# decawave-rf.net
KiCad netlist of a schematic drawn in Altium Designer
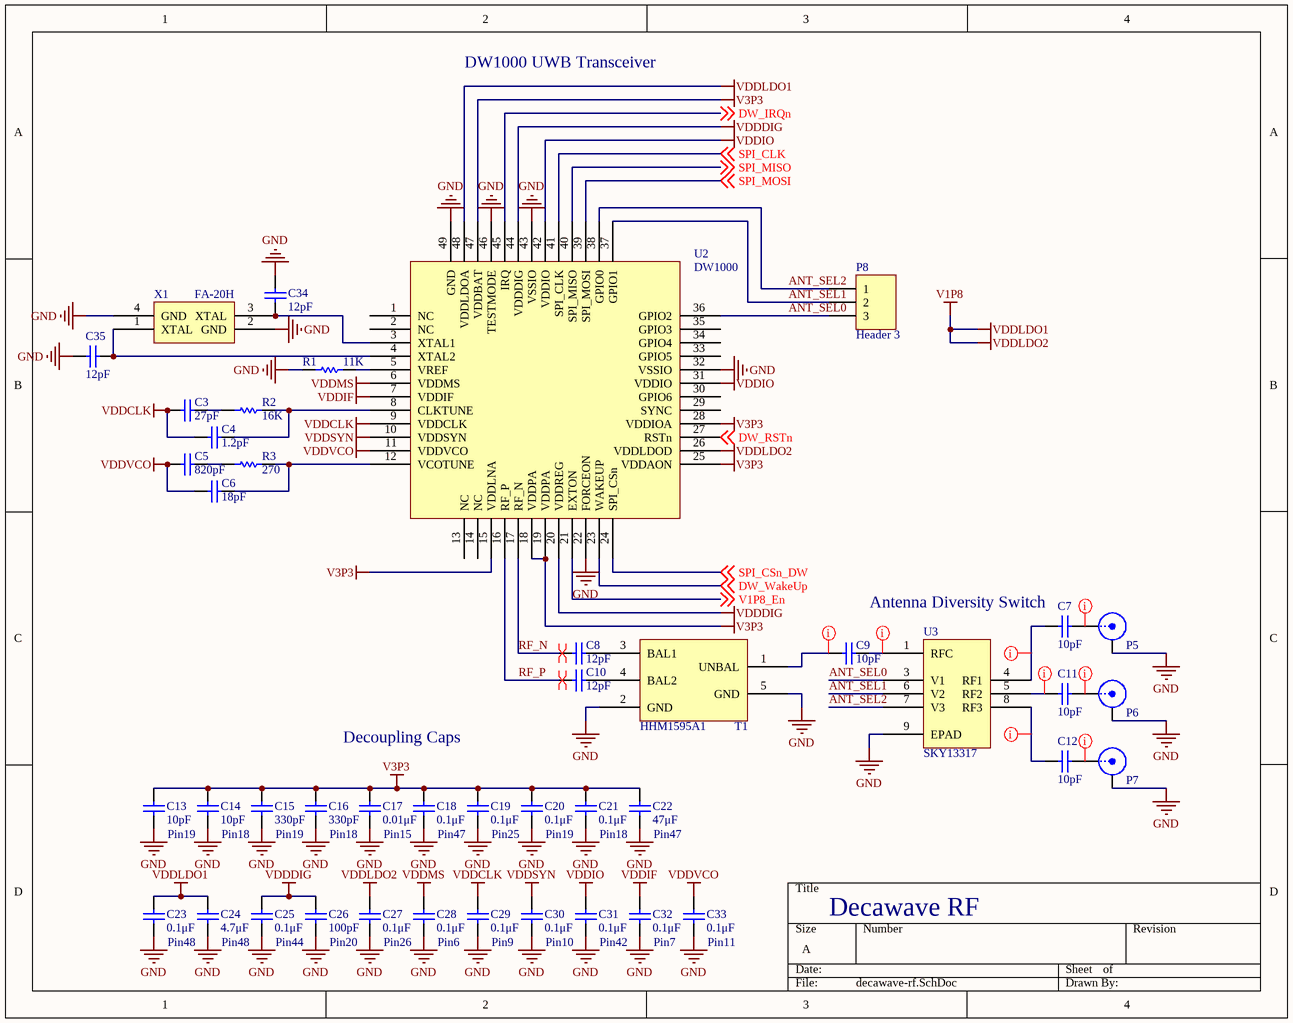
[diagram p0: decawave-rf.SchDoc]

(export (version "E")
  (design (tool "Eeschema 10.0.6"))
  (components
    (comp (ref "C3")
      (value "27pF")
      (footprint "0402")
      (description "Capacitor (Semiconductor SIM Model)")
      (fields
        (field (name "DISTPARTNO") "490-5869-1-ND")
        (field (name "MANPARTNO") "GRM1555C1H270JA01D")
        (field (name "PUBLISHER") "Altium Limited")
      )
      (libsource (lib "decawave-lib") (part "Cap Chip"))
    )
    (comp (ref "C4")
      (value "1.2pF")
      (footprint "0402")
      (description "Capacitor (Semiconductor SIM Model)")
      (fields
        (field (name "DISTPARTNO") "490-6209-1-ND")
        (field (name "MANPARTNO") "GRM1555C1H1R2BA01D")
        (field (name "PUBLISHER") "Altium Limited")
      )
      (libsource (lib "decawave-lib") (part "Cap Chip"))
    )
    (comp (ref "C5")
      (value "820pF")
      (footprint "0402")
      (description "Capacitor (Semiconductor SIM Model)")
      (fields
        (field (name "DISTPARTNO") "490-3250-1-ND")
        (field (name "MANPARTNO") "GRM155R71H821KA01D")
        (field (name "PUBLISHER") "Altium Limited")
      )
      (libsource (lib "decawave-lib") (part "Cap Chip"))
    )
    (comp (ref "C6")
      (value "18pF")
      (footprint "0402")
      (description "Capacitor (Semiconductor SIM Model)")
      (fields
        (field (name "DISTPARTNO") "490-5858-1-ND")
        (field (name "MANPARTNO") "GRM1555C1H180JA01D")
        (field (name "PUBLISHER") "Altium Limited")
      )
      (libsource (lib "decawave-lib") (part "Cap Chip"))
    )
    (comp (ref "C7")
      (value "10pF")
      (footprint "0402")
      (description "Capacitor (Semiconductor SIM Model)")
      (fields
        (field (name "DISTPARTNO") "490-3113-1-ND")
        (field (name "MANPARTNO") "GJM1555C1H100JB01D")
        (field (name "PUBLISHER") "Altium Limited")
      )
      (libsource (lib "decawave-lib") (part "Cap Chip"))
    )
    (comp (ref "C8")
      (value "12pF")
      (footprint "0402")
      (description "Capacitor (Semiconductor SIM Model)")
      (fields
        (field (name "DISTPARTNO") "490-3115-1-ND")
        (field (name "MANPARTNO") "GJM1555C1H120JB01D")
        (field (name "PUBLISHER") "Altium Limited")
      )
      (libsource (lib "decawave-lib") (part "Cap Chip"))
    )
    (comp (ref "C9")
      (value "10pF")
      (footprint "0402")
      (description "Capacitor (Semiconductor SIM Model)")
      (fields
        (field (name "DISTPARTNO") "490-3113-1-ND")
        (field (name "MANPARTNO") "GJM1555C1H100JB01D")
        (field (name "PUBLISHER") "Altium Limited")
      )
      (libsource (lib "decawave-lib") (part "Cap Chip"))
    )
    (comp (ref "C10")
      (value "12pF")
      (footprint "0402")
      (description "Capacitor (Semiconductor SIM Model)")
      (fields
        (field (name "DISTPARTNO") "490-3115-1-ND")
        (field (name "MANPARTNO") "GJM1555C1H120JB01D")
        (field (name "PUBLISHER") "Altium Limited")
      )
      (libsource (lib "decawave-lib") (part "Cap Chip"))
    )
    (comp (ref "C11")
      (value "10pF")
      (footprint "0402")
      (description "Capacitor (Semiconductor SIM Model)")
      (fields
        (field (name "DISTPARTNO") "490-3113-1-ND")
        (field (name "MANPARTNO") "GJM1555C1H100JB01D")
        (field (name "PUBLISHER") "Altium Limited")
      )
      (libsource (lib "decawave-lib") (part "Cap Chip"))
    )
    (comp (ref "C12")
      (value "10pF")
      (footprint "0402")
      (description "Capacitor (Semiconductor SIM Model)")
      (fields
        (field (name "DISTPARTNO") "490-3113-1-ND")
        (field (name "MANPARTNO") "GJM1555C1H100JB01D")
        (field (name "PUBLISHER") "Altium Limited")
      )
      (libsource (lib "decawave-lib") (part "Cap Chip"))
    )
    (comp (ref "C13")
      (value "10pF")
      (footprint "0402")
      (description "Capacitor (Semiconductor SIM Model)")
      (fields
        (field (name "PINPLACEMENT") "Pin19")
        (field (name "DISTPARTNO") "490-3113-1-ND")
        (field (name "MANPARTNO") "GJM1555C1H100JB01D")
        (field (name "PUBLISHER") "Altium Limited")
      )
      (libsource (lib "decawave-lib") (part "Cap Chip"))
    )
    (comp (ref "C14")
      (value "10pF")
      (footprint "0402")
      (description "Capacitor (Semiconductor SIM Model)")
      (fields
        (field (name "PINPLACEMENT") "Pin18")
        (field (name "DISTPARTNO") "490-3113-1-ND")
        (field (name "MANPARTNO") "GJM1555C1H100JB01D")
        (field (name "PUBLISHER") "Altium Limited")
      )
      (libsource (lib "decawave-lib") (part "Cap Chip"))
    )
    (comp (ref "C15")
      (value "330pF")
      (footprint "0402")
      (description "Capacitor (Semiconductor SIM Model)")
      (fields
        (field (name "PINPLACEMENT") "Pin19")
        (field (name "DISTPARTNO") "490-1295-1-ND")
        (field (name "MANPARTNO") "GRM1555C1H331JA01D")
        (field (name "PUBLISHER") "Altium Limited")
      )
      (libsource (lib "decawave-lib") (part "Cap Chip"))
    )
    (comp (ref "C16")
      (value "330pF")
      (footprint "0402")
      (description "Capacitor (Semiconductor SIM Model)")
      (fields
        (field (name "PINPLACEMENT") "Pin18")
        (field (name "DISTPARTNO") "490-1295-1-ND")
        (field (name "MANPARTNO") "GRM1555C1H331JA01D")
        (field (name "PUBLISHER") "Altium Limited")
      )
      (libsource (lib "decawave-lib") (part "Cap Chip"))
    )
    (comp (ref "C17")
      (value "0.01μF")
      (footprint "0402")
      (description "Capacitor (Semiconductor SIM Model)")
      (fields
        (field (name "PINPLACEMENT") "Pin15")
        (field (name "DISTPARTNO") "490-1312-1-ND")
        (field (name "MANPARTNO") "GRM155R71E103KA01D")
        (field (name "PUBLISHER") "Altium Limited")
      )
      (libsource (lib "decawave-lib") (part "Cap Chip"))
    )
    (comp (ref "C18")
      (value "0.1μF")
      (footprint "0402")
      (description "Capacitor (Semiconductor SIM Model)")
      (fields
        (field (name "PINPLACEMENT") "Pin47")
        (field (name "DISTPARTNO") "490-3261-1-ND")
        (field (name "MANPARTNO") "GRM155R71C104KA88D")
        (field (name "PUBLISHER") "Altium Limited")
      )
      (libsource (lib "decawave-lib") (part "Cap Chip"))
    )
    (comp (ref "C19")
      (value "0.1μF")
      (footprint "0402")
      (description "Capacitor (Semiconductor SIM Model)")
      (fields
        (field (name "PINPLACEMENT") "Pin25")
        (field (name "DISTPARTNO") "490-3261-1-ND")
        (field (name "MANPARTNO") "GRM155R71C104KA88D")
        (field (name "PUBLISHER") "Altium Limited")
      )
      (libsource (lib "decawave-lib") (part "Cap Chip"))
    )
    (comp (ref "C20")
      (value "0.1μF")
      (footprint "0402")
      (description "Capacitor (Semiconductor SIM Model)")
      (fields
        (field (name "PINPLACEMENT") "Pin19")
        (field (name "DISTPARTNO") "490-3261-1-ND")
        (field (name "MANPARTNO") "GRM155R71C104KA88D")
        (field (name "PUBLISHER") "Altium Limited")
      )
      (libsource (lib "decawave-lib") (part "Cap Chip"))
    )
    (comp (ref "C21")
      (value "0.1μF")
      (footprint "0402")
      (description "Capacitor (Semiconductor SIM Model)")
      (fields
        (field (name "PINPLACEMENT") "Pin18")
        (field (name "DISTPARTNO") "490-3261-1-ND")
        (field (name "MANPARTNO") "GRM155R71C104KA88D")
        (field (name "PUBLISHER") "Altium Limited")
      )
      (libsource (lib "decawave-lib") (part "Cap Chip"))
    )
    (comp (ref "C22")
      (value "47μF")
      (footprint "0805")
      (description "Capacitor (Semiconductor SIM Model)")
      (fields
        (field (name "PINPLACEMENT") "Pin47")
        (field (name "DISTPARTNO") "1276-2420-1-ND")
        (field (name "MANPARTNO") "CL21A476MQCLRNC")
        (field (name "PUBLISHER") "Altium Limited")
      )
      (libsource (lib "decawave-lib") (part "Cap Chip"))
    )
    (comp (ref "C23")
      (value "0.1μF")
      (footprint "0402")
      (description "Capacitor (Semiconductor SIM Model)")
      (fields
        (field (name "PINPLACEMENT") "Pin48")
        (field (name "DISTPARTNO") "490-3261-1-ND")
        (field (name "MANPARTNO") "GRM155R71C104KA88D")
        (field (name "PUBLISHER") "Altium Limited")
      )
      (libsource (lib "decawave-lib") (part "Cap Chip"))
    )
    (comp (ref "C24")
      (value "4.7μF")
      (footprint "0402")
      (description "Capacitor (Semiconductor SIM Model)")
      (fields
        (field (name "PINPLACEMENT") "Pin48")
        (field (name "DISTPARTNO") "445-8023-1-ND")
        (field (name "MANPARTNO") "C1005X5R1A475M050BC")
        (field (name "PUBLISHER") "Altium Limited")
      )
      (libsource (lib "decawave-lib") (part "Cap Chip"))
    )
    (comp (ref "C25")
      (value "0.1μF")
      (footprint "0402")
      (description "Capacitor (Semiconductor SIM Model)")
      (fields
        (field (name "PINPLACEMENT") "Pin44")
        (field (name "DISTPARTNO") "490-3261-1-ND")
        (field (name "MANPARTNO") "GRM155R71C104KA88D")
        (field (name "PUBLISHER") "Altium Limited")
      )
      (libsource (lib "decawave-lib") (part "Cap Chip"))
    )
    (comp (ref "C26")
      (value "100pF")
      (footprint "0402")
      (description "Capacitor (Semiconductor SIM Model)")
      (fields
        (field (name "PINPLACEMENT") "Pin20")
        (field (name "DISTPARTNO") "490-5922-1-ND")
        (field (name "MANPARTNO") "GRM1555C1H101JA01D")
        (field (name "PUBLISHER") "Altium Limited")
      )
      (libsource (lib "decawave-lib") (part "Cap Chip"))
    )
    (comp (ref "C27")
      (value "0.1μF")
      (footprint "0402")
      (description "Capacitor (Semiconductor SIM Model)")
      (fields
        (field (name "PINPLACEMENT") "Pin26")
        (field (name "DISTPARTNO") "490-3261-1-ND")
        (field (name "MANPARTNO") "GRM155R71C104KA88D")
        (field (name "PUBLISHER") "Altium Limited")
      )
      (libsource (lib "decawave-lib") (part "Cap Chip"))
    )
    (comp (ref "C28")
      (value "0.1μF")
      (footprint "0402")
      (description "Capacitor (Semiconductor SIM Model)")
      (fields
        (field (name "PINPLACEMENT") "Pin6")
        (field (name "DISTPARTNO") "490-3261-1-ND")
        (field (name "MANPARTNO") "GRM155R71C104KA88D")
        (field (name "PUBLISHER") "Altium Limited")
      )
      (libsource (lib "decawave-lib") (part "Cap Chip"))
    )
    (comp (ref "C29")
      (value "0.1μF")
      (footprint "0402")
      (description "Capacitor (Semiconductor SIM Model)")
      (fields
        (field (name "PINPLACEMENT") "Pin9")
        (field (name "DISTPARTNO") "490-3261-1-ND")
        (field (name "MANPARTNO") "GRM155R71C104KA88D")
        (field (name "PUBLISHER") "Altium Limited")
      )
      (libsource (lib "decawave-lib") (part "Cap Chip"))
    )
    (comp (ref "C30")
      (value "0.1μF")
      (footprint "0402")
      (description "Capacitor (Semiconductor SIM Model)")
      (fields
        (field (name "PINPLACEMENT") "Pin10")
        (field (name "DISTPARTNO") "490-3261-1-ND")
        (field (name "MANPARTNO") "GRM155R71C104KA88D")
        (field (name "PUBLISHER") "Altium Limited")
      )
      (libsource (lib "decawave-lib") (part "Cap Chip"))
    )
    (comp (ref "C31")
      (value "0.1μF")
      (footprint "0402")
      (description "Capacitor (Semiconductor SIM Model)")
      (fields
        (field (name "PINPLACEMENT") "Pin42")
        (field (name "DISTPARTNO") "490-3261-1-ND")
        (field (name "MANPARTNO") "GRM155R71C104KA88D")
        (field (name "PUBLISHER") "Altium Limited")
      )
      (libsource (lib "decawave-lib") (part "Cap Chip"))
    )
    (comp (ref "C32")
      (value "0.1μF")
      (footprint "0402")
      (description "Capacitor (Semiconductor SIM Model)")
      (fields
        (field (name "PINPLACEMENT") "Pin7")
        (field (name "DISTPARTNO") "490-3261-1-ND")
        (field (name "MANPARTNO") "GRM155R71C104KA88D")
        (field (name "PUBLISHER") "Altium Limited")
      )
      (libsource (lib "decawave-lib") (part "Cap Chip"))
    )
    (comp (ref "C33")
      (value "0.1μF")
      (footprint "0402")
      (description "Capacitor (Semiconductor SIM Model)")
      (fields
        (field (name "PINPLACEMENT") "Pin11")
        (field (name "DISTPARTNO") "490-3261-1-ND")
        (field (name "MANPARTNO") "GRM155R71C104KA88D")
        (field (name "PUBLISHER") "Altium Limited")
      )
      (libsource (lib "decawave-lib") (part "Cap Chip"))
    )
    (comp (ref "C34")
      (value "12pF")
      (footprint "0402")
      (description "Capacitor (Semiconductor SIM Model)")
      (fields
        (field (name "DISTPARTNO") "490-3115-1-ND")
        (field (name "MANPARTNO") "GJM1555C1H120JB01D")
        (field (name "PUBLISHER") "Altium Limited")
      )
      (libsource (lib "decawave-lib") (part "Cap Chip"))
    )
    (comp (ref "C35")
      (value "12pF")
      (footprint "0402")
      (description "Capacitor (Semiconductor SIM Model)")
      (fields
        (field (name "DISTPARTNO") "490-3115-1-ND")
        (field (name "MANPARTNO") "GJM1555C1H120JB01D")
        (field (name "PUBLISHER") "Altium Limited")
      )
      (libsource (lib "decawave-lib") (part "Cap Chip"))
    )
    (comp (ref "P5")
      (value "SMA")
      (footprint "SMA_EDGE")
      (fields (field (name "DISTPARTNO") "CONSMA003.062-ND") (field (name "MANPARTNO") "CONSMA003.062"))
      (libsource (lib "decawave-lib") (part "SMA"))
    )
    (comp (ref "P6")
      (value "SMA")
      (footprint "SMA_EDGE")
      (fields (field (name "DISTPARTNO") "CONSMA003.062-ND") (field (name "MANPARTNO") "CONSMA003.062"))
      (libsource (lib "decawave-lib") (part "SMA"))
    )
    (comp (ref "P7")
      (value "SMA")
      (footprint "SMA_EDGE")
      (fields (field (name "DISTPARTNO") "CONSMA003.062-ND") (field (name "MANPARTNO") "CONSMA003.062"))
      (libsource (lib "decawave-lib") (part "SMA"))
    )
    (comp (ref "P8")
      (value "Header 3")
      (footprint "HDR1X3")
      (description "Header, 3-Pin")
      (fields (field (name "PUBLISHER") "Altium Limited"))
      (libsource (lib "Miscellaneous Connectors") (part "Header 3"))
    )
    (comp (ref "R1")
      (value "11K")
      (footprint "0402")
      (description "Surface-mount resistor")
      (fields
        (field (name "DISTPARTNO") "P11.0KLCT-ND")
        (field (name "MANPARTNO") "ERJ-2RKF1102X")
        (field (name "PUBLISHER") "Altium Limited")
      )
      (libsource (lib "decawave-lib") (part "Res Chip"))
    )
    (comp (ref "R2")
      (value "16K")
      (footprint "0402")
      (description "Surface-mount resistor")
      (fields
        (field (name "DISTPARTNO") "P16.0KLCT-ND")
        (field (name "MANPARTNO") "ERJ-2RKF1602X")
        (field (name "PUBLISHER") "Altium Limited")
      )
      (libsource (lib "decawave-lib") (part "Res Chip"))
    )
    (comp (ref "R3")
      (value "270")
      (footprint "0402")
      (description "Surface-mount resistor")
      (fields
        (field (name "DISTPARTNO") "P270LCT-ND")
        (field (name "MANPARTNO") "ERJ-2RKF2700X")
        (field (name "PUBLISHER") "Altium Limited")
      )
      (libsource (lib "decawave-lib") (part "Res Chip"))
    )
    (comp (ref "T1")
      (value "HHM1595A1")
      (footprint "HHM 0805")
      (description "UWB Balun")
      (fields (field (name "DISTPARTNO") "445-3387-1-ND"))
      (libsource (lib "decawave-lib") (part "HHM1595A1"))
    )
    (comp (ref "U2")
      (value "DW1000")
      (footprint "48QFN-EP")
      (fields (field (name "DISTPARTNO") "1479-1001-1-ND") (field (name "MANPARTNO") "DW1000-I-TR13"))
      (libsource (lib "decawave-lib") (part "DW1000"))
    )
    (comp (ref "U3")
      (value "SKY13317")
      (footprint "MLPQ-UT-8")
      (description "SP3T RF Switch")
      (fields (field (name "DISTPARTNO") "863-1056-1-ND") (field (name "MANPARTNO") "SKY13317-373LF"))
      (libsource (lib "decawave-lib") (part "SKY13317"))
    )
    (comp (ref "X1")
      (value "FA-20H")
      (footprint "FA-20H")
      (description "2.5 mm x 2.0 mm SMD Crystal")
      (fields (field (name "DISTPARTNO") "SER3631CT-ND") (field (name "MANPARTNO") "FA-20H 38.4000MF10Z-AS3"))
      (libsource (lib "decawave-lib") (part "FA-20H"))
    )
  )
  (nets
    (net (code "1") (name "/ANT_SEL0") (class "Default")
      (node (ref "P8") (pin "3") (pinfunction "3_3") (pintype "passive"))
      (node (ref "U2") (pin "36") (pinfunction "GPIO2_36") (pintype "passive"))
      (node (ref "U3") (pin "3") (pinfunction "V1_3") (pintype "passive"))
    )
    (net (code "2") (name "/ANT_SEL1") (class "Default")
      (node (ref "P8") (pin "2") (pinfunction "2_2") (pintype "passive"))
      (node (ref "U2") (pin "37") (pinfunction "GPIO1_37") (pintype "passive"))
      (node (ref "U3") (pin "6") (pinfunction "V2_6") (pintype "passive"))
    )
    (net (code "3") (name "/ANT_SEL2") (class "Default")
      (node (ref "P8") (pin "1") (pinfunction "1_1") (pintype "passive"))
      (node (ref "U2") (pin "38") (pinfunction "GPIO0_38") (pintype "passive"))
      (node (ref "U3") (pin "7") (pinfunction "V3_7") (pintype "passive"))
    )
    (net (code "4") (name "/RF_N") (class "Default")
      (node (ref "C8") (pin "1") (pinfunction "1_1") (pintype "passive"))
      (node (ref "U2") (pin "17") (pinfunction "RF_N_17") (pintype "passive"))
    )
    (net (code "5") (name "/RF_P") (class "Default")
      (node (ref "C10") (pin "1") (pinfunction "1_1") (pintype "passive"))
      (node (ref "U2") (pin "16") (pinfunction "RF_P_16") (pintype "passive"))
    )
    (net (code "6") (name "DW_IRQn") (class "Default")
      (node (ref "U2") (pin "45") (pinfunction "IRQ_45") (pintype "passive"))
    )
    (net (code "7") (name "DW_RSTn") (class "Default")
      (node (ref "U2") (pin "27") (pinfunction "RSTn_27") (pintype "passive"))
    )
    (net (code "8") (name "DW_WakeUp") (class "Default")
      (node (ref "U2") (pin "23") (pinfunction "WAKEUP_23") (pintype "passive"))
    )
    (net (code "9") (name "GND") (class "Default")
      (node (ref "C13") (pin "2") (pinfunction "2_2") (pintype "passive"))
      (node (ref "C14") (pin "2") (pinfunction "2_2") (pintype "passive"))
      (node (ref "C15") (pin "2") (pinfunction "2_2") (pintype "passive"))
      (node (ref "C16") (pin "2") (pinfunction "2_2") (pintype "passive"))
      (node (ref "C17") (pin "2") (pinfunction "2_2") (pintype "passive"))
      (node (ref "C18") (pin "2") (pinfunction "2_2") (pintype "passive"))
      (node (ref "C19") (pin "2") (pinfunction "2_2") (pintype "passive"))
      (node (ref "C20") (pin "2") (pinfunction "2_2") (pintype "passive"))
      (node (ref "C21") (pin "2") (pinfunction "2_2") (pintype "passive"))
      (node (ref "C22") (pin "2") (pinfunction "2_2") (pintype "passive"))
      (node (ref "C23") (pin "2") (pinfunction "2_2") (pintype "passive"))
      (node (ref "C24") (pin "2") (pinfunction "2_2") (pintype "passive"))
      (node (ref "C25") (pin "2") (pinfunction "2_2") (pintype "passive"))
      (node (ref "C26") (pin "2") (pinfunction "2_2") (pintype "passive"))
      (node (ref "C27") (pin "2") (pinfunction "2_2") (pintype "passive"))
      (node (ref "C28") (pin "2") (pinfunction "2_2") (pintype "passive"))
      (node (ref "C29") (pin "2") (pinfunction "2_2") (pintype "passive"))
      (node (ref "C30") (pin "2") (pinfunction "2_2") (pintype "passive"))
      (node (ref "C31") (pin "2") (pinfunction "2_2") (pintype "passive"))
      (node (ref "C32") (pin "2") (pinfunction "2_2") (pintype "passive"))
      (node (ref "C33") (pin "2") (pinfunction "2_2") (pintype "passive"))
      (node (ref "C34") (pin "1") (pinfunction "1_1") (pintype "passive"))
      (node (ref "C35") (pin "1") (pinfunction "1_1") (pintype "passive"))
      (node (ref "P5") (pin "2") (pinfunction "Y_2") (pintype "passive"))
      (node (ref "P6") (pin "2") (pinfunction "Y_2") (pintype "passive"))
      (node (ref "P7") (pin "2") (pinfunction "Y_2") (pintype "passive"))
      (node (ref "R1") (pin "1") (pinfunction "1_1") (pintype "passive"))
      (node (ref "T1") (pin "2") (pinfunction "GND_2") (pintype "passive"))
      (node (ref "T1") (pin "5") (pinfunction "GND_5") (pintype "passive"))
      (node (ref "U2") (pin "22") (pinfunction "FORCEON_22") (pintype "passive"))
      (node (ref "U2") (pin "32") (pinfunction "VSSIO_32") (pintype "passive"))
      (node (ref "U2") (pin "43") (pinfunction "VSSIO_43") (pintype "passive"))
      (node (ref "U2") (pin "46") (pinfunction "TESTMODE_46") (pintype "passive"))
      (node (ref "U2") (pin "49") (pinfunction "GND_49") (pintype "passive"))
      (node (ref "U3") (pin "9") (pinfunction "EPAD_9") (pintype "passive"))
      (node (ref "X1") (pin "2") (pinfunction "GND_2") (pintype "passive"))
      (node (ref "X1") (pin "4") (pinfunction "GND_4") (pintype "passive"))
    )
    (net (code "10") (name "Net-(C3-Pad2)") (class "Default")
      (node (ref "C3") (pin "2") (pinfunction "2_2") (pintype "passive"))
      (node (ref "R2") (pin "1") (pinfunction "1_1") (pintype "passive"))
    )
    (net (code "11") (name "Net-(C5-Pad2)") (class "Default")
      (node (ref "C5") (pin "2") (pinfunction "2_2") (pintype "passive"))
      (node (ref "R3") (pin "1") (pinfunction "1_1") (pintype "passive"))
    )
    (net (code "12") (name "Net-(P5-X)") (class "Default")
      (node (ref "C7") (pin "2") (pinfunction "2_2") (pintype "passive"))
      (node (ref "P5") (pin "1") (pinfunction "X_1") (pintype "passive"))
    )
    (net (code "13") (name "Net-(P6-X)") (class "Default")
      (node (ref "C11") (pin "2") (pinfunction "2_2") (pintype "passive"))
      (node (ref "P6") (pin "1") (pinfunction "X_1") (pintype "passive"))
    )
    (net (code "14") (name "Net-(P7-X)") (class "Default")
      (node (ref "C12") (pin "2") (pinfunction "2_2") (pintype "passive"))
      (node (ref "P7") (pin "1") (pinfunction "X_1") (pintype "passive"))
    )
    (net (code "15") (name "Net-(T1-BAL1)") (class "Default")
      (node (ref "C8") (pin "2") (pinfunction "2_2") (pintype "passive"))
      (node (ref "T1") (pin "3") (pinfunction "BAL1_3") (pintype "passive"))
    )
    (net (code "16") (name "Net-(T1-BAL2)") (class "Default")
      (node (ref "C10") (pin "2") (pinfunction "2_2") (pintype "passive"))
      (node (ref "T1") (pin "4") (pinfunction "BAL2_4") (pintype "passive"))
    )
    (net (code "17") (name "Net-(T1-UNBAL)") (class "Default")
      (node (ref "C9") (pin "1") (pinfunction "1_1") (pintype "passive"))
      (node (ref "T1") (pin "1") (pinfunction "UNBAL_1") (pintype "passive"))
    )
    (net (code "18") (name "Net-(U2-CLKTUNE)") (class "Default")
      (node (ref "C4") (pin "2") (pinfunction "2_2") (pintype "passive"))
      (node (ref "R2") (pin "2") (pinfunction "2_2") (pintype "passive"))
      (node (ref "U2") (pin "8") (pinfunction "CLKTUNE_8") (pintype "passive"))
    )
    (net (code "19") (name "Net-(U2-VCOTUNE)") (class "Default")
      (node (ref "C6") (pin "2") (pinfunction "2_2") (pintype "passive"))
      (node (ref "R3") (pin "2") (pinfunction "2_2") (pintype "passive"))
      (node (ref "U2") (pin "12") (pinfunction "VCOTUNE_12") (pintype "passive"))
    )
    (net (code "20") (name "Net-(U2-VREF)") (class "Default")
      (node (ref "R1") (pin "2") (pinfunction "2_2") (pintype "passive"))
      (node (ref "U2") (pin "5") (pinfunction "VREF_5") (pintype "passive"))
    )
    (net (code "21") (name "Net-(U2-XTAL1)") (class "Default")
      (node (ref "C34") (pin "2") (pinfunction "2_2") (pintype "passive"))
      (node (ref "U2") (pin "3") (pinfunction "XTAL1_3") (pintype "passive"))
      (node (ref "X1") (pin "3") (pinfunction "XTAL_3") (pintype "passive"))
    )
    (net (code "22") (name "Net-(U2-XTAL2)") (class "Default")
      (node (ref "C35") (pin "2") (pinfunction "2_2") (pintype "passive"))
      (node (ref "U2") (pin "4") (pinfunction "XTAL2_4") (pintype "passive"))
      (node (ref "X1") (pin "1") (pinfunction "XTAL_1") (pintype "passive"))
    )
    (net (code "23") (name "Net-(U3-RF1)") (class "Default")
      (node (ref "C7") (pin "1") (pinfunction "1_1") (pintype "passive"))
      (node (ref "U3") (pin "4") (pinfunction "RF1_4") (pintype "passive"))
    )
    (net (code "24") (name "Net-(U3-RF2)") (class "Default")
      (node (ref "C11") (pin "1") (pinfunction "1_1") (pintype "passive"))
      (node (ref "U3") (pin "5") (pinfunction "RF2_5") (pintype "passive"))
    )
    (net (code "25") (name "Net-(U3-RF3)") (class "Default")
      (node (ref "C12") (pin "1") (pinfunction "1_1") (pintype "passive"))
      (node (ref "U3") (pin "8") (pinfunction "RF3_8") (pintype "passive"))
    )
    (net (code "26") (name "Net-(U3-RFC)") (class "Default")
      (node (ref "C9") (pin "2") (pinfunction "2_2") (pintype "passive"))
      (node (ref "U3") (pin "1") (pinfunction "RFC_1") (pintype "passive"))
    )
    (net (code "27") (name "SPI_CLK") (class "Default")
      (node (ref "U2") (pin "41") (pinfunction "SPI_CLK_41") (pintype "passive"))
    )
    (net (code "28") (name "SPI_CSn_DW") (class "Default")
      (node (ref "U2") (pin "24") (pinfunction "SPI_CSn_24") (pintype "passive"))
    )
    (net (code "29") (name "SPI_MISO") (class "Default")
      (node (ref "U2") (pin "40") (pinfunction "SPI_MISO_40") (pintype "passive"))
    )
    (net (code "30") (name "SPI_MOSI") (class "Default")
      (node (ref "U2") (pin "39") (pinfunction "SPI_MOSI_39") (pintype "passive"))
    )
    (net (code "31") (name "V1P8") (class "Default")
      (node (ref "C23") (pin "1") (pinfunction "1_1") (pintype "passive"))
      (node (ref "C24") (pin "1") (pinfunction "1_1") (pintype "passive"))
      (node (ref "C27") (pin "1") (pinfunction "1_1") (pintype "passive"))
      (node (ref "U2") (pin "26") (pinfunction "VDDLDOD_26") (pintype "passive"))
      (node (ref "U2") (pin "48") (pinfunction "VDDLDOA_48") (pintype "passive"))
    )
    (net (code "32") (name "V1P8_En") (class "Default")
      (node (ref "U2") (pin "21") (pinfunction "EXTON_21") (pintype "passive"))
    )
    (net (code "33") (name "V3P3") (class "Default")
      (node (ref "C13") (pin "1") (pinfunction "1_1") (pintype "passive"))
      (node (ref "C14") (pin "1") (pinfunction "1_1") (pintype "passive"))
      (node (ref "C15") (pin "1") (pinfunction "1_1") (pintype "passive"))
      (node (ref "C16") (pin "1") (pinfunction "1_1") (pintype "passive"))
      (node (ref "C17") (pin "1") (pinfunction "1_1") (pintype "passive"))
      (node (ref "C18") (pin "1") (pinfunction "1_1") (pintype "passive"))
      (node (ref "C19") (pin "1") (pinfunction "1_1") (pintype "passive"))
      (node (ref "C20") (pin "1") (pinfunction "1_1") (pintype "passive"))
      (node (ref "C21") (pin "1") (pinfunction "1_1") (pintype "passive"))
      (node (ref "C22") (pin "1") (pinfunction "1_1") (pintype "passive"))
      (node (ref "U2") (pin "15") (pinfunction "VDDLNA_15") (pintype "passive"))
      (node (ref "U2") (pin "18") (pinfunction "VDDPA_18") (pintype "passive"))
      (node (ref "U2") (pin "19") (pinfunction "VDDPA_19") (pintype "passive"))
      (node (ref "U2") (pin "25") (pinfunction "VDDAON_25") (pintype "passive"))
      (node (ref "U2") (pin "28") (pinfunction "VDDIOA_28") (pintype "passive"))
      (node (ref "U2") (pin "47") (pinfunction "VDDBAT_47") (pintype "passive"))
    )
    (net (code "34") (name "VDDCLK") (class "Default")
      (node (ref "C29") (pin "1") (pinfunction "1_1") (pintype "passive"))
      (node (ref "C3") (pin "1") (pinfunction "1_1") (pintype "passive"))
      (node (ref "C4") (pin "1") (pinfunction "1_1") (pintype "passive"))
      (node (ref "U2") (pin "9") (pinfunction "VDDCLK_9") (pintype "passive"))
    )
    (net (code "35") (name "VDDDIG") (class "Default")
      (node (ref "C25") (pin "1") (pinfunction "1_1") (pintype "passive"))
      (node (ref "C26") (pin "1") (pinfunction "1_1") (pintype "passive"))
      (node (ref "U2") (pin "20") (pinfunction "VDDREG_20") (pintype "passive"))
      (node (ref "U2") (pin "44") (pinfunction "VDDDIG_44") (pintype "passive"))
    )
    (net (code "36") (name "VDDIF") (class "Default")
      (node (ref "C32") (pin "1") (pinfunction "1_1") (pintype "passive"))
      (node (ref "U2") (pin "7") (pinfunction "VDDIF_7") (pintype "passive"))
    )
    (net (code "37") (name "VDDIO") (class "Default")
      (node (ref "C31") (pin "1") (pinfunction "1_1") (pintype "passive"))
      (node (ref "U2") (pin "31") (pinfunction "VDDIO_31") (pintype "passive"))
      (node (ref "U2") (pin "42") (pinfunction "VDDIO_42") (pintype "passive"))
    )
    (net (code "38") (name "VDDMS") (class "Default")
      (node (ref "C28") (pin "1") (pinfunction "1_1") (pintype "passive"))
      (node (ref "U2") (pin "6") (pinfunction "VDDMS_6") (pintype "passive"))
    )
    (net (code "39") (name "VDDSYN") (class "Default")
      (node (ref "C30") (pin "1") (pinfunction "1_1") (pintype "passive"))
      (node (ref "U2") (pin "10") (pinfunction "VDDSYN_10") (pintype "passive"))
    )
    (net (code "40") (name "VDDVCO") (class "Default")
      (node (ref "C33") (pin "1") (pinfunction "1_1") (pintype "passive"))
      (node (ref "C5") (pin "1") (pinfunction "1_1") (pintype "passive"))
      (node (ref "C6") (pin "1") (pinfunction "1_1") (pintype "passive"))
      (node (ref "U2") (pin "11") (pinfunction "VDDVCO_11") (pintype "passive"))
    )
    (net (code "41") (name "unconnected-(U2-GPIO3-Pad35)") (class "Default")
      (node (ref "U2") (pin "35") (pinfunction "GPIO3_35") (pintype "passive"))
    )
    (net (code "42") (name "unconnected-(U2-GPIO4-Pad34)") (class "Default")
      (node (ref "U2") (pin "34") (pinfunction "GPIO4_34") (pintype "passive"))
    )
    (net (code "43") (name "unconnected-(U2-GPIO5-Pad33)") (class "Default")
      (node (ref "U2") (pin "33") (pinfunction "GPIO5_33") (pintype "passive"))
    )
    (net (code "44") (name "unconnected-(U2-GPIO6-Pad30)") (class "Default")
      (node (ref "U2") (pin "30") (pinfunction "GPIO6_30") (pintype "passive"))
    )
    (net (code "45") (name "unconnected-(U2-NC-Pad1)") (class "Default")
      (node (ref "U2") (pin "1") (pinfunction "NC_1") (pintype "passive"))
    )
    (net (code "46") (name "unconnected-(U2-NC-Pad2)") (class "Default")
      (node (ref "U2") (pin "2") (pinfunction "NC_2") (pintype "passive"))
    )
    (net (code "47") (name "unconnected-(U2-NC-Pad13)") (class "Default")
      (node (ref "U2") (pin "13") (pinfunction "NC_13") (pintype "passive"))
    )
    (net (code "48") (name "unconnected-(U2-NC-Pad14)") (class "Default")
      (node (ref "U2") (pin "14") (pinfunction "NC_14") (pintype "passive"))
    )
    (net (code "49") (name "unconnected-(U2-SYNC-Pad29)") (class "Default")
      (node (ref "U2") (pin "29") (pinfunction "SYNC_29") (pintype "passive"))
    )
  )
)
